# board_disp.net
KiCad netlist of a schematic drawn in EAGLE
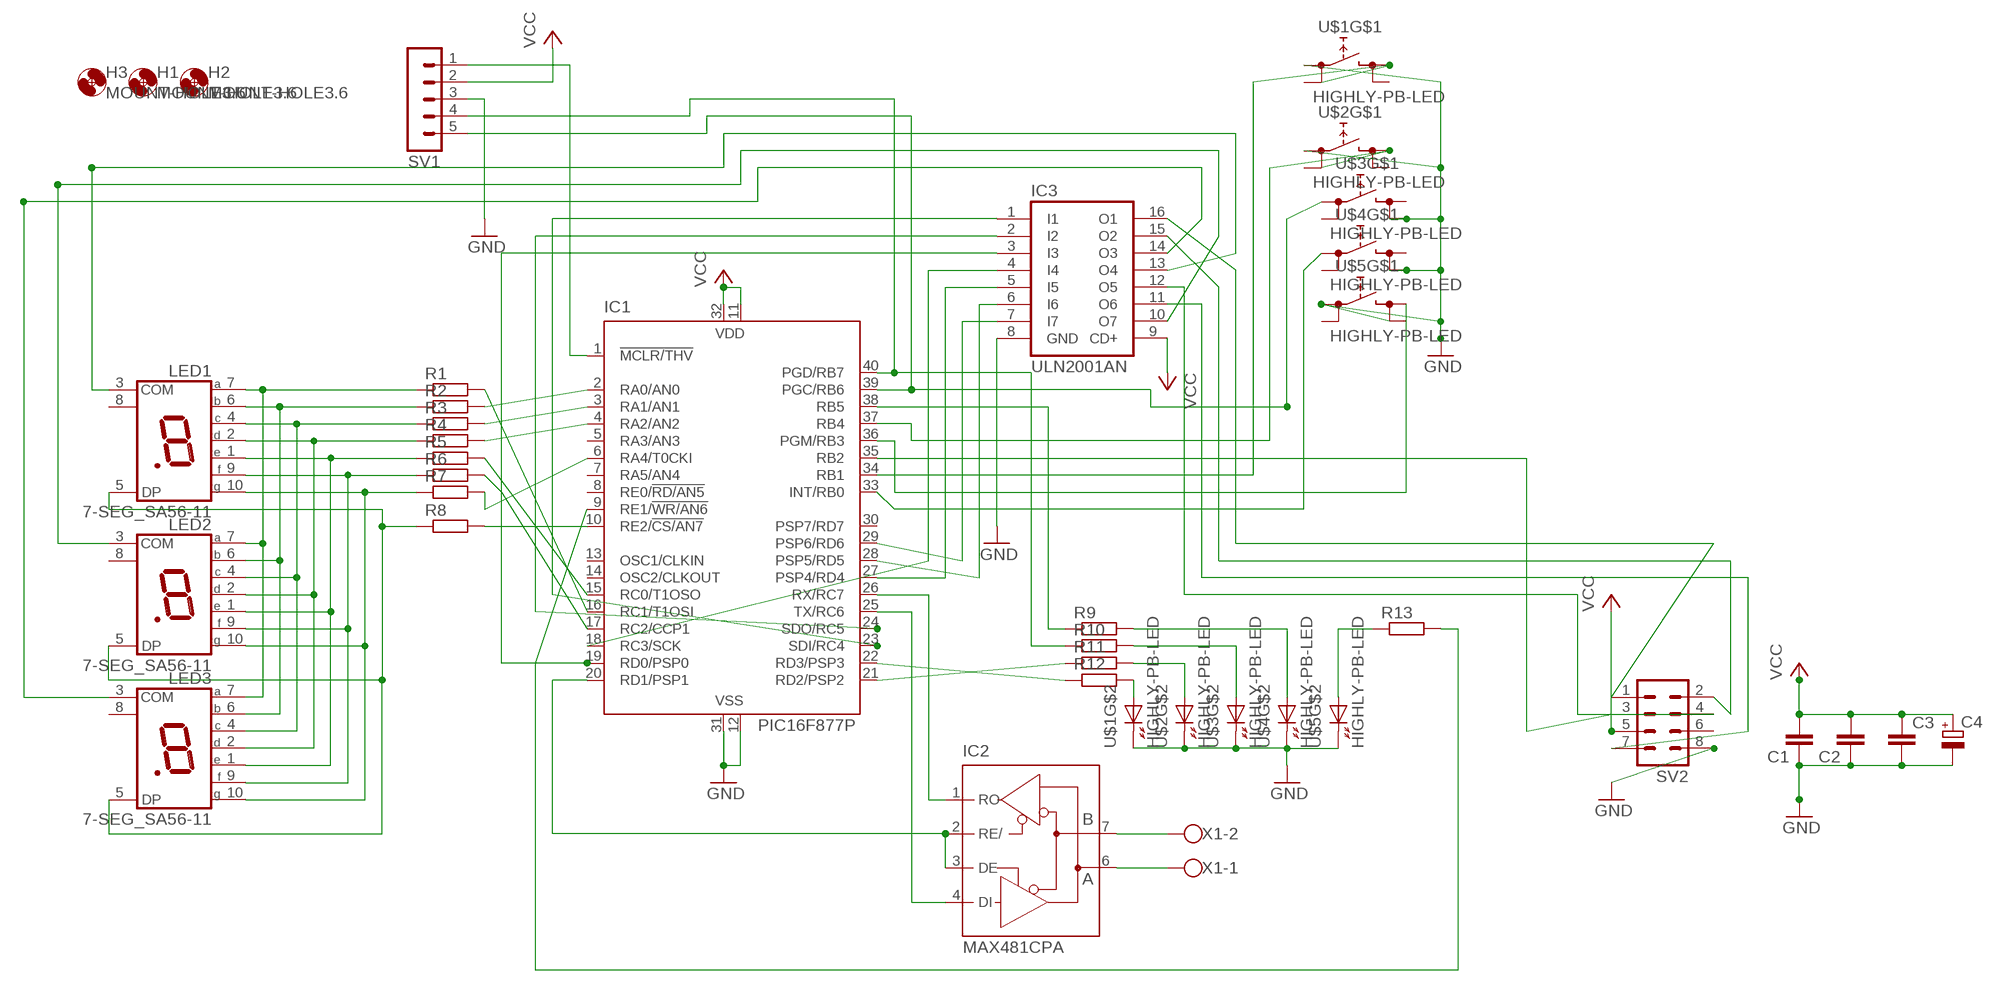
[diagram p0: schematic, sheet 1]

(export (version "E")
  (design (tool "Eeschema 10.0.6"))
  (components
    (comp (ref "C1")
      (value "C-EU025_050-025X075")
      (footprint "eagle-import:C025_050-025X075")
      (libsource (lib "eagle-import") (part "C-EU025_050-025X075"))
    )
    (comp (ref "C2")
      (value "C-EU025_050-025X075")
      (footprint "eagle-import:C025_050-025X075")
      (libsource (lib "eagle-import") (part "C-EU025_050-025X075"))
    )
    (comp (ref "C3")
      (value "C-EU025_050-025X075")
      (footprint "eagle-import:C025_050-025X075")
      (libsource (lib "eagle-import") (part "C-EU025_050-025X075"))
    )
    (comp (ref "C4")
      (value "CPOL-EUE3.5-8")
      (footprint "eagle-import:E3,5-8")
      (libsource (lib "eagle-import") (part "CPOL-EUE3.5-8"))
    )
    (comp (ref "H1")
      (value "MOUNT-HOLE3.6")
      (footprint "eagle-import:3,6")
      (libsource (lib "eagle-import") (part "MOUNT-HOLE3.6"))
    )
    (comp (ref "H2")
      (value "MOUNT-HOLE3.6")
      (footprint "eagle-import:3,6")
      (libsource (lib "eagle-import") (part "MOUNT-HOLE3.6"))
    )
    (comp (ref "H3")
      (value "MOUNT-HOLE3.6")
      (footprint "eagle-import:3,6")
      (libsource (lib "eagle-import") (part "MOUNT-HOLE3.6"))
    )
    (comp (ref "IC1")
      (value "PIC16F877P")
      (footprint "eagle-import:DIL40")
      (fields (field (name "MF") "MICROCHIP") (field (name "MPN") "PIC16F877-04/P"))
      (libsource (lib "eagle-import") (part "PIC16F87P7"))
    )
    (comp (ref "IC2")
      (value "MAX481CPA")
      (footprint "eagle-import:DIL08")
      (fields (field (name "MPN") "MAX481CPA+"))
      (libsource (lib "eagle-import") (part "MAX481CPA"))
    )
    (comp (ref "IC3")
      (value "ULN2001AN")
      (footprint "eagle-import:DIL16")
      (libsource (lib "eagle-import") (part "ULN2001AN"))
    )
    (comp (ref "LED1")
      (value "7-SEG_SA56-11")
      (footprint "eagle-import:SA56-11")
      (libsource (lib "eagle-import") (part "7-SEG_SA56-11"))
    )
    (comp (ref "LED2")
      (value "7-SEG_SA56-11")
      (footprint "eagle-import:SA56-11")
      (libsource (lib "eagle-import") (part "7-SEG_SA56-11"))
    )
    (comp (ref "LED3")
      (value "7-SEG_SA56-11")
      (footprint "eagle-import:SA56-11")
      (libsource (lib "eagle-import") (part "7-SEG_SA56-11"))
    )
    (comp (ref "R1")
      (value "R-EU_0207/10")
      (footprint "eagle-import:0207_10")
      (libsource (lib "eagle-import") (part "R-EU_0207/10"))
    )
    (comp (ref "R2")
      (value "R-EU_0207/10")
      (footprint "eagle-import:0207_10")
      (libsource (lib "eagle-import") (part "R-EU_0207/10"))
    )
    (comp (ref "R3")
      (value "R-EU_0207/10")
      (footprint "eagle-import:0207_10")
      (libsource (lib "eagle-import") (part "R-EU_0207/10"))
    )
    (comp (ref "R4")
      (value "R-EU_0207/10")
      (footprint "eagle-import:0207_10")
      (libsource (lib "eagle-import") (part "R-EU_0207/10"))
    )
    (comp (ref "R5")
      (value "R-EU_0207/10")
      (footprint "eagle-import:0207_10")
      (libsource (lib "eagle-import") (part "R-EU_0207/10"))
    )
    (comp (ref "R6")
      (value "R-EU_0207/10")
      (footprint "eagle-import:0207_10")
      (libsource (lib "eagle-import") (part "R-EU_0207/10"))
    )
    (comp (ref "R7")
      (value "R-EU_0207/10")
      (footprint "eagle-import:0207_10")
      (libsource (lib "eagle-import") (part "R-EU_0207/10"))
    )
    (comp (ref "R8")
      (value "R-EU_0207/10")
      (footprint "eagle-import:0207_10")
      (libsource (lib "eagle-import") (part "R-EU_0207/10"))
    )
    (comp (ref "R9")
      (value "R-EU_0207/10")
      (footprint "eagle-import:0207_10")
      (libsource (lib "eagle-import") (part "R-EU_0207/10"))
    )
    (comp (ref "R10")
      (value "R-EU_0207/10")
      (footprint "eagle-import:0207_10")
      (libsource (lib "eagle-import") (part "R-EU_0207/10"))
    )
    (comp (ref "R11")
      (value "R-EU_0207/10")
      (footprint "eagle-import:0207_10")
      (libsource (lib "eagle-import") (part "R-EU_0207/10"))
    )
    (comp (ref "R12")
      (value "R-EU_0207/10")
      (footprint "eagle-import:0207_10")
      (libsource (lib "eagle-import") (part "R-EU_0207/10"))
    )
    (comp (ref "R13")
      (value "R-EU_0207/10")
      (footprint "eagle-import:0207_10")
      (libsource (lib "eagle-import") (part "R-EU_0207/10"))
    )
    (comp (ref "SV1")
      (value "MA05-1")
      (footprint "eagle-import:MA05-1")
      (libsource (lib "eagle-import") (part "MA05-1"))
    )
    (comp (ref "SV2")
      (value "MA04-2")
      (footprint "eagle-import:MA04-2")
      (libsource (lib "eagle-import") (part "MA04-2"))
    )
    (comp (ref "U$1")
      (value "HIGHLY-PB-LED")
      (footprint "eagle-import:HIGHLY-PUSHBUTTON")
      (libsource (lib "eagle-import") (part "HIGHLY-PB-LED"))
    )
    (comp (ref "U$2")
      (value "HIGHLY-PB-LED")
      (footprint "eagle-import:HIGHLY-PUSHBUTTON")
      (libsource (lib "eagle-import") (part "HIGHLY-PB-LED"))
    )
    (comp (ref "U$3")
      (value "HIGHLY-PB-LED")
      (footprint "eagle-import:HIGHLY-PUSHBUTTON")
      (libsource (lib "eagle-import") (part "HIGHLY-PB-LED"))
    )
    (comp (ref "U$4")
      (value "HIGHLY-PB-LED")
      (footprint "eagle-import:HIGHLY-PUSHBUTTON")
      (libsource (lib "eagle-import") (part "HIGHLY-PB-LED"))
    )
    (comp (ref "U$5")
      (value "HIGHLY-PB-LED")
      (footprint "eagle-import:HIGHLY-PUSHBUTTON")
      (libsource (lib "eagle-import") (part "HIGHLY-PB-LED"))
    )
    (comp (ref "X1")
      (value "PASSO3")
      (footprint "eagle-import:PASSO3")
      (fields (field (name "MPN") "237-102"))
      (libsource (lib "eagle-import") (part "PASSO3"))
    )
  )
  (nets
    (net (code "1") (name "GND") (class "Default")
      (node (ref "C1") (pin "1") (pinfunction "1_1") (pintype "passive"))
      (node (ref "C2") (pin "1") (pinfunction "1_1") (pintype "passive"))
      (node (ref "C3") (pin "2") (pinfunction "2_2") (pintype "passive"))
      (node (ref "C4") (pin "-") (pinfunction "-_-") (pintype "passive"))
      (node (ref "IC1") (pin "12") (pinfunction "VSS_12") (pintype "power_in"))
      (node (ref "IC1") (pin "31") (pinfunction "VSS_31") (pintype "power_in"))
      (node (ref "IC3") (pin "8") (pinfunction "GND_8") (pintype "power_in"))
      (node (ref "SV1") (pin "3") (pinfunction "3_3") (pintype "passive"))
      (node (ref "SV2") (pin "8") (pinfunction "8_8") (pintype "passive"))
      (node (ref "U$1") (pin "1A") (pinfunction "0_1A") (pintype "passive"))
      (node (ref "U$1") (pin "K") (pinfunction "K_K") (pintype "passive"))
      (node (ref "U$2") (pin "1A") (pinfunction "0_1A") (pintype "passive"))
      (node (ref "U$2") (pin "K") (pinfunction "K_K") (pintype "passive"))
      (node (ref "U$3") (pin "2B") (pinfunction "1_2B") (pintype "passive"))
      (node (ref "U$3") (pin "K") (pinfunction "K_K") (pintype "passive"))
      (node (ref "U$4") (pin "2B") (pinfunction "1_2B") (pintype "passive"))
      (node (ref "U$4") (pin "K") (pinfunction "K_K") (pintype "passive"))
      (node (ref "U$5") (pin "1A") (pinfunction "0_1A") (pintype "passive"))
      (node (ref "U$5") (pin "K") (pinfunction "K_K") (pintype "passive"))
    )
    (net (code "2") (name "Net-(IC1-INT{slash}RB0)") (class "Default")
      (node (ref "IC1") (pin "33") (pinfunction "INT/RB0_33") (pintype "bidirectional"))
      (node (ref "U$4") (pin "1A") (pinfunction "0_1A") (pintype "passive"))
    )
    (net (code "3") (name "Net-(IC1-PGC{slash}RB6)") (class "Default")
      (node (ref "IC1") (pin "39") (pinfunction "PGC/RB6_39") (pintype "bidirectional"))
      (node (ref "SV1") (pin "5") (pinfunction "5_5") (pintype "passive"))
      (node (ref "U$3") (pin "1A") (pinfunction "0_1A") (pintype "passive"))
    )
    (net (code "4") (name "Net-(IC1-PGD{slash}RB7)") (class "Default")
      (node (ref "IC1") (pin "40") (pinfunction "PGD/RB7_40") (pintype "bidirectional"))
      (node (ref "R10") (pin "1") (pinfunction "1_1") (pintype "passive"))
      (node (ref "SV1") (pin "4") (pinfunction "4_4") (pintype "passive"))
    )
    (net (code "5") (name "Net-(IC1-PGM{slash}RB3)") (class "Default")
      (node (ref "IC1") (pin "36") (pinfunction "PGM/RB3_36") (pintype "bidirectional"))
      (node (ref "U$5") (pin "2A") (pinfunction "1_2A") (pintype "passive"))
    )
    (net (code "6") (name "Net-(IC1-PSP4{slash}RD4)") (class "Default")
      (node (ref "IC1") (pin "27") (pinfunction "PSP4/RD4_27") (pintype "bidirectional"))
      (node (ref "IC3") (pin "5") (pinfunction "I5_5") (pintype "input"))
    )
    (net (code "7") (name "Net-(IC1-PSP5{slash}RD5)") (class "Default")
      (node (ref "IC1") (pin "28") (pinfunction "PSP5/RD5_28") (pintype "bidirectional"))
      (node (ref "IC3") (pin "6") (pinfunction "I6_6") (pintype "input"))
    )
    (net (code "8") (name "Net-(IC1-PSP6{slash}RD6)") (class "Default")
      (node (ref "IC1") (pin "29") (pinfunction "PSP6/RD6_29") (pintype "bidirectional"))
      (node (ref "IC3") (pin "7") (pinfunction "I7_7") (pintype "input"))
    )
    (net (code "9") (name "Net-(IC1-RA0{slash}AN0)") (class "Default")
      (node (ref "IC1") (pin "2") (pinfunction "RA0/AN0_2") (pintype "bidirectional"))
      (node (ref "R2") (pin "2") (pinfunction "2_2") (pintype "passive"))
    )
    (net (code "10") (name "Net-(IC1-RA1{slash}AN1)") (class "Default")
      (node (ref "IC1") (pin "3") (pinfunction "RA1/AN1_3") (pintype "bidirectional"))
      (node (ref "R3") (pin "2") (pinfunction "2_2") (pintype "passive"))
    )
    (net (code "11") (name "Net-(IC1-RA2{slash}AN2)") (class "Default")
      (node (ref "IC1") (pin "4") (pinfunction "RA2/AN2_4") (pintype "bidirectional"))
      (node (ref "R4") (pin "2") (pinfunction "2_2") (pintype "passive"))
    )
    (net (code "12") (name "Net-(IC1-RA4{slash}T0CKI)") (class "Default")
      (node (ref "IC1") (pin "6") (pinfunction "RA4/T0CKI_6") (pintype "bidirectional"))
      (node (ref "R7") (pin "2") (pinfunction "2_2") (pintype "passive"))
    )
    (net (code "13") (name "Net-(IC1-RB1)") (class "Default")
      (node (ref "IC1") (pin "34") (pinfunction "RB1_34") (pintype "bidirectional"))
      (node (ref "U$1") (pin "2A") (pinfunction "1_2A") (pintype "passive"))
    )
    (net (code "14") (name "Net-(IC1-RB2)") (class "Default")
      (node (ref "IC1") (pin "35") (pinfunction "RB2_35") (pintype "bidirectional"))
      (node (ref "SV2") (pin "3") (pinfunction "3_3") (pintype "passive"))
    )
    (net (code "15") (name "Net-(IC1-RB4)") (class "Default")
      (node (ref "IC1") (pin "37") (pinfunction "RB4_37") (pintype "bidirectional"))
      (node (ref "U$2") (pin "2A") (pinfunction "1_2A") (pintype "passive"))
    )
    (net (code "16") (name "Net-(IC1-RB5)") (class "Default")
      (node (ref "IC1") (pin "38") (pinfunction "RB5_38") (pintype "bidirectional"))
      (node (ref "R9") (pin "1") (pinfunction "1_1") (pintype "passive"))
    )
    (net (code "17") (name "Net-(IC1-RC0{slash}T1OSO)") (class "Default")
      (node (ref "IC1") (pin "15") (pinfunction "RC0/T1OSO_15") (pintype "bidirectional"))
      (node (ref "R5") (pin "2") (pinfunction "2_2") (pintype "passive"))
    )
    (net (code "18") (name "Net-(IC1-RC1{slash}T1OSI)") (class "Default")
      (node (ref "IC1") (pin "16") (pinfunction "RC1/T1OSI_16") (pintype "bidirectional"))
      (node (ref "R1") (pin "2") (pinfunction "2_2") (pintype "passive"))
    )
    (net (code "19") (name "Net-(IC1-RC2{slash}CCP1)") (class "Default")
      (node (ref "IC1") (pin "17") (pinfunction "RC2/CCP1_17") (pintype "bidirectional"))
      (node (ref "R6") (pin "2") (pinfunction "2_2") (pintype "passive"))
    )
    (net (code "20") (name "Net-(IC1-RC3{slash}SCK)") (class "Default")
      (node (ref "IC1") (pin "18") (pinfunction "RC3/SCK_18") (pintype "bidirectional"))
      (node (ref "IC3") (pin "4") (pinfunction "I4_4") (pintype "input"))
    )
    (net (code "21") (name "Net-(IC1-RD0{slash}PSP0)") (class "Default")
      (node (ref "IC1") (pin "19") (pinfunction "RD0/PSP0_19") (pintype "bidirectional"))
      (node (ref "IC3") (pin "3") (pinfunction "I3_3") (pintype "input"))
    )
    (net (code "22") (name "Net-(IC1-RD1{slash}PSP1)") (class "Default")
      (node (ref "IC1") (pin "20") (pinfunction "RD1/PSP1_20") (pintype "bidirectional"))
      (node (ref "IC2") (pin "2") (pinfunction "RE/_2") (pintype "input"))
      (node (ref "IC2") (pin "3") (pinfunction "DE_3") (pintype "input"))
    )
    (net (code "23") (name "Net-(IC1-RD2{slash}PSP2)") (class "Default")
      (node (ref "IC1") (pin "21") (pinfunction "RD2/PSP2_21") (pintype "bidirectional"))
      (node (ref "R11") (pin "1") (pinfunction "1_1") (pintype "passive"))
    )
    (net (code "24") (name "Net-(IC1-RD3{slash}PSP3)") (class "Default")
      (node (ref "IC1") (pin "22") (pinfunction "RD3/PSP3_22") (pintype "bidirectional"))
      (node (ref "R12") (pin "1") (pinfunction "1_1") (pintype "passive"))
    )
    (net (code "25") (name "Net-(IC1-RE1{slash}~{WR{slash}AN6})") (class "Default")
      (node (ref "IC1") (pin "9") (pinfunction "RE1/~{WR/AN6}_9") (pintype "bidirectional"))
      (node (ref "R13") (pin "2") (pinfunction "2_2") (pintype "passive"))
    )
    (net (code "26") (name "Net-(IC1-RE2{slash}~{CS{slash}AN7})") (class "Default")
      (node (ref "IC1") (pin "10") (pinfunction "RE2/~{CS/AN7}_10") (pintype "bidirectional"))
      (node (ref "R8") (pin "2") (pinfunction "2_2") (pintype "passive"))
    )
    (net (code "27") (name "Net-(IC1-RX{slash}RC7)") (class "Default")
      (node (ref "IC1") (pin "26") (pinfunction "RX/RC7_26") (pintype "bidirectional"))
      (node (ref "IC2") (pin "1") (pinfunction "RO_1") (pintype "output"))
    )
    (net (code "28") (name "Net-(IC1-SDI{slash}RC4)") (class "Default")
      (node (ref "IC1") (pin "23") (pinfunction "SDI/RC4_23") (pintype "bidirectional"))
      (node (ref "IC3") (pin "1") (pinfunction "I1_1") (pintype "input"))
    )
    (net (code "29") (name "Net-(IC1-SDO{slash}RC5)") (class "Default")
      (node (ref "IC1") (pin "24") (pinfunction "SDO/RC5_24") (pintype "bidirectional"))
      (node (ref "IC3") (pin "2") (pinfunction "I2_2") (pintype "input"))
    )
    (net (code "30") (name "Net-(IC1-TX{slash}RC6)") (class "Default")
      (node (ref "IC1") (pin "25") (pinfunction "TX/RC6_25") (pintype "bidirectional"))
      (node (ref "IC2") (pin "4") (pinfunction "DI_4") (pintype "input"))
    )
    (net (code "31") (name "Net-(IC1-~{MCLR{slash}THV})") (class "Default")
      (node (ref "IC1") (pin "1") (pinfunction "~{MCLR/THV}_1") (pintype "input"))
      (node (ref "SV1") (pin "1") (pinfunction "1_1") (pintype "passive"))
    )
    (net (code "32") (name "Net-(IC2A-A)") (class "Default")
      (node (ref "IC2") (pin "6") (pinfunction "A_6") (pintype "passive"))
      (node (ref "X1") (pin "1") (pinfunction "KL_1") (pintype "passive"))
    )
    (net (code "33") (name "Net-(IC2A-B)") (class "Default")
      (node (ref "IC2") (pin "7") (pinfunction "B_7") (pintype "passive"))
      (node (ref "X1") (pin "2") (pinfunction "KL_2") (pintype "passive"))
    )
    (net (code "34") (name "Net-(IC3-O1)") (class "Default")
      (node (ref "IC3") (pin "16") (pinfunction "O1_16") (pintype "open_collector"))
      (node (ref "SV2") (pin "1") (pinfunction "1_1") (pintype "passive"))
    )
    (net (code "35") (name "Net-(IC3-O2)") (class "Default")
      (node (ref "IC3") (pin "15") (pinfunction "O2_15") (pintype "open_collector"))
      (node (ref "SV2") (pin "2") (pinfunction "2_2") (pintype "passive"))
    )
    (net (code "36") (name "Net-(IC3-O3)") (class "Default")
      (node (ref "IC3") (pin "14") (pinfunction "O3_14") (pintype "open_collector"))
      (node (ref "LED3") (pin "3") (pinfunction "COM_3") (pintype "passive"))
    )
    (net (code "37") (name "Net-(IC3-O4)") (class "Default")
      (node (ref "IC3") (pin "13") (pinfunction "O4_13") (pintype "open_collector"))
      (node (ref "LED1") (pin "3") (pinfunction "COM_3") (pintype "passive"))
    )
    (net (code "38") (name "Net-(IC3-O5)") (class "Default")
      (node (ref "IC3") (pin "12") (pinfunction "O5_12") (pintype "open_collector"))
      (node (ref "SV2") (pin "4") (pinfunction "4_4") (pintype "passive"))
    )
    (net (code "39") (name "Net-(IC3-O6)") (class "Default")
      (node (ref "IC3") (pin "11") (pinfunction "O6_11") (pintype "open_collector"))
      (node (ref "SV2") (pin "7") (pinfunction "7_7") (pintype "passive"))
    )
    (net (code "40") (name "Net-(IC3-O7)") (class "Default")
      (node (ref "IC3") (pin "10") (pinfunction "O7_10") (pintype "open_collector"))
      (node (ref "LED2") (pin "3") (pinfunction "COM_3") (pintype "passive"))
    )
    (net (code "41") (name "Net-(LED1-A)") (class "Default")
      (node (ref "LED1") (pin "7") (pinfunction "A_7") (pintype "passive"))
      (node (ref "LED2") (pin "7") (pinfunction "A_7") (pintype "passive"))
      (node (ref "LED3") (pin "7") (pinfunction "A_7") (pintype "passive"))
      (node (ref "R1") (pin "1") (pinfunction "1_1") (pintype "passive"))
    )
    (net (code "42") (name "Net-(LED1-B)") (class "Default")
      (node (ref "LED1") (pin "6") (pinfunction "B_6") (pintype "passive"))
      (node (ref "LED2") (pin "6") (pinfunction "B_6") (pintype "passive"))
      (node (ref "LED3") (pin "6") (pinfunction "B_6") (pintype "passive"))
      (node (ref "R2") (pin "1") (pinfunction "1_1") (pintype "passive"))
    )
    (net (code "43") (name "Net-(LED1-C)") (class "Default")
      (node (ref "LED1") (pin "4") (pinfunction "C_4") (pintype "passive"))
      (node (ref "LED2") (pin "4") (pinfunction "C_4") (pintype "passive"))
      (node (ref "LED3") (pin "4") (pinfunction "C_4") (pintype "passive"))
      (node (ref "R3") (pin "1") (pinfunction "1_1") (pintype "passive"))
    )
    (net (code "44") (name "Net-(LED1-D)") (class "Default")
      (node (ref "LED1") (pin "2") (pinfunction "D_2") (pintype "passive"))
      (node (ref "LED2") (pin "2") (pinfunction "D_2") (pintype "passive"))
      (node (ref "LED3") (pin "2") (pinfunction "D_2") (pintype "passive"))
      (node (ref "R4") (pin "1") (pinfunction "1_1") (pintype "passive"))
    )
    (net (code "45") (name "Net-(LED1-DP)") (class "Default")
      (node (ref "LED1") (pin "5") (pinfunction "DP_5") (pintype "passive"))
      (node (ref "LED2") (pin "5") (pinfunction "DP_5") (pintype "passive"))
      (node (ref "LED3") (pin "5") (pinfunction "DP_5") (pintype "passive"))
      (node (ref "R8") (pin "1") (pinfunction "1_1") (pintype "passive"))
    )
    (net (code "46") (name "Net-(LED1-E)") (class "Default")
      (node (ref "LED1") (pin "1") (pinfunction "E_1") (pintype "passive"))
      (node (ref "LED2") (pin "1") (pinfunction "E_1") (pintype "passive"))
      (node (ref "LED3") (pin "1") (pinfunction "E_1") (pintype "passive"))
      (node (ref "R5") (pin "1") (pinfunction "1_1") (pintype "passive"))
    )
    (net (code "47") (name "Net-(LED1-F)") (class "Default")
      (node (ref "LED1") (pin "9") (pinfunction "F_9") (pintype "passive"))
      (node (ref "LED2") (pin "9") (pinfunction "F_9") (pintype "passive"))
      (node (ref "LED3") (pin "9") (pinfunction "F_9") (pintype "passive"))
      (node (ref "R6") (pin "1") (pinfunction "1_1") (pintype "passive"))
    )
    (net (code "48") (name "Net-(LED1-G)") (class "Default")
      (node (ref "LED1") (pin "10") (pinfunction "G_10") (pintype "passive"))
      (node (ref "LED2") (pin "10") (pinfunction "G_10") (pintype "passive"))
      (node (ref "LED3") (pin "10") (pinfunction "G_10") (pintype "passive"))
      (node (ref "R7") (pin "1") (pinfunction "1_1") (pintype "passive"))
    )
    (net (code "49") (name "Net-(R9-Pad2)") (class "Default")
      (node (ref "R9") (pin "2") (pinfunction "2_2") (pintype "passive"))
      (node (ref "U$4") (pin "A") (pinfunction "A_A") (pintype "passive"))
    )
    (net (code "50") (name "Net-(R10-Pad2)") (class "Default")
      (node (ref "R10") (pin "2") (pinfunction "2_2") (pintype "passive"))
      (node (ref "U$3") (pin "A") (pinfunction "A_A") (pintype "passive"))
    )
    (net (code "51") (name "Net-(R11-Pad2)") (class "Default")
      (node (ref "R11") (pin "2") (pinfunction "2_2") (pintype "passive"))
      (node (ref "U$2") (pin "A") (pinfunction "A_A") (pintype "passive"))
    )
    (net (code "52") (name "Net-(R12-Pad2)") (class "Default")
      (node (ref "R12") (pin "2") (pinfunction "2_2") (pintype "passive"))
      (node (ref "U$1") (pin "A") (pinfunction "A_A") (pintype "passive"))
    )
    (net (code "53") (name "Net-(R13-Pad1)") (class "Default")
      (node (ref "R13") (pin "1") (pinfunction "1_1") (pintype "passive"))
      (node (ref "U$5") (pin "A") (pinfunction "A_A") (pintype "passive"))
    )
    (net (code "54") (name "VCC") (class "Default")
      (node (ref "C1") (pin "2") (pinfunction "2_2") (pintype "passive"))
      (node (ref "C2") (pin "2") (pinfunction "2_2") (pintype "passive"))
      (node (ref "C3") (pin "1") (pinfunction "1_1") (pintype "passive"))
      (node (ref "C4") (pin "+") (pinfunction "+_+") (pintype "passive"))
      (node (ref "IC1") (pin "11") (pinfunction "VDD_11") (pintype "power_in"))
      (node (ref "IC1") (pin "32") (pinfunction "VDD_32") (pintype "power_in"))
      (node (ref "IC3") (pin "9") (pinfunction "CD+_9") (pintype "passive"))
      (node (ref "SV1") (pin "2") (pinfunction "2_2") (pintype "passive"))
      (node (ref "SV2") (pin "5") (pinfunction "5_5") (pintype "passive"))
    )
    (net (code "55") (name "unconnected-(IC1-OSC1{slash}CLKIN-Pad13)") (class "Default")
      (node (ref "IC1") (pin "13") (pinfunction "OSC1/CLKIN_13") (pintype "input"))
    )
    (net (code "56") (name "unconnected-(IC1-OSC2{slash}CLKOUT-Pad14)") (class "Default")
      (node (ref "IC1") (pin "14") (pinfunction "OSC2/CLKOUT_14") (pintype "output"))
    )
    (net (code "57") (name "unconnected-(IC1-PSP7{slash}RD7-Pad30)") (class "Default")
      (node (ref "IC1") (pin "30") (pinfunction "PSP7/RD7_30") (pintype "bidirectional"))
    )
    (net (code "58") (name "unconnected-(IC1-RA3{slash}AN3-Pad5)") (class "Default")
      (node (ref "IC1") (pin "5") (pinfunction "RA3/AN3_5") (pintype "bidirectional"))
    )
    (net (code "59") (name "unconnected-(IC1-RA5{slash}AN4-Pad7)") (class "Default")
      (node (ref "IC1") (pin "7") (pinfunction "RA5/AN4_7") (pintype "bidirectional"))
    )
    (net (code "60") (name "unconnected-(IC1-RE0{slash}~{RD{slash}AN5}-Pad8)") (class "Default")
      (node (ref "IC1") (pin "8") (pinfunction "RE0/~{RD/AN5}_8") (pintype "bidirectional"))
    )
    (net (code "61") (name "unconnected-(LED1-COM-Pad8)") (class "Default")
      (node (ref "LED1") (pin "8") (pinfunction "COM_8") (pintype "passive"))
    )
    (net (code "62") (name "unconnected-(LED2-COM-Pad8)") (class "Default")
      (node (ref "LED2") (pin "8") (pinfunction "COM_8") (pintype "passive"))
    )
    (net (code "63") (name "unconnected-(LED3-COM-Pad8)") (class "Default")
      (node (ref "LED3") (pin "8") (pinfunction "COM_8") (pintype "passive"))
    )
    (net (code "64") (name "unconnected-(SV2-Pad6)") (class "Default")
      (node (ref "SV2") (pin "6") (pinfunction "6_6") (pintype "passive"))
    )
    (net (code "65") (name "unconnected-(U$1A-0-Pad1B)") (class "Default")
      (node (ref "U$1") (pin "1B") (pinfunction "0_1B") (pintype "passive"))
    )
    (net (code "66") (name "unconnected-(U$1A-1-Pad2B)") (class "Default")
      (node (ref "U$1") (pin "2B") (pinfunction "1_2B") (pintype "passive"))
    )
    (net (code "67") (name "unconnected-(U$2A-0-Pad1B)") (class "Default")
      (node (ref "U$2") (pin "1B") (pinfunction "0_1B") (pintype "passive"))
    )
    (net (code "68") (name "unconnected-(U$2A-1-Pad2B)") (class "Default")
      (node (ref "U$2") (pin "2B") (pinfunction "1_2B") (pintype "passive"))
    )
    (net (code "69") (name "unconnected-(U$3A-0-Pad1B)") (class "Default")
      (node (ref "U$3") (pin "1B") (pinfunction "0_1B") (pintype "passive"))
    )
    (net (code "70") (name "unconnected-(U$3A-1-Pad2A)") (class "Default")
      (node (ref "U$3") (pin "2A") (pinfunction "1_2A") (pintype "passive"))
    )
    (net (code "71") (name "unconnected-(U$4A-0-Pad1B)") (class "Default")
      (node (ref "U$4") (pin "1B") (pinfunction "0_1B") (pintype "passive"))
    )
    (net (code "72") (name "unconnected-(U$4A-1-Pad2A)") (class "Default")
      (node (ref "U$4") (pin "2A") (pinfunction "1_2A") (pintype "passive"))
    )
    (net (code "73") (name "unconnected-(U$5A-0-Pad1B)") (class "Default")
      (node (ref "U$5") (pin "1B") (pinfunction "0_1B") (pintype "passive"))
    )
    (net (code "74") (name "unconnected-(U$5A-1-Pad2B)") (class "Default")
      (node (ref "U$5") (pin "2B") (pinfunction "1_2B") (pintype "passive"))
    )
  )
)
